# Add-OnV20-final.net
KiCad netlist of a schematic drawn in EAGLE
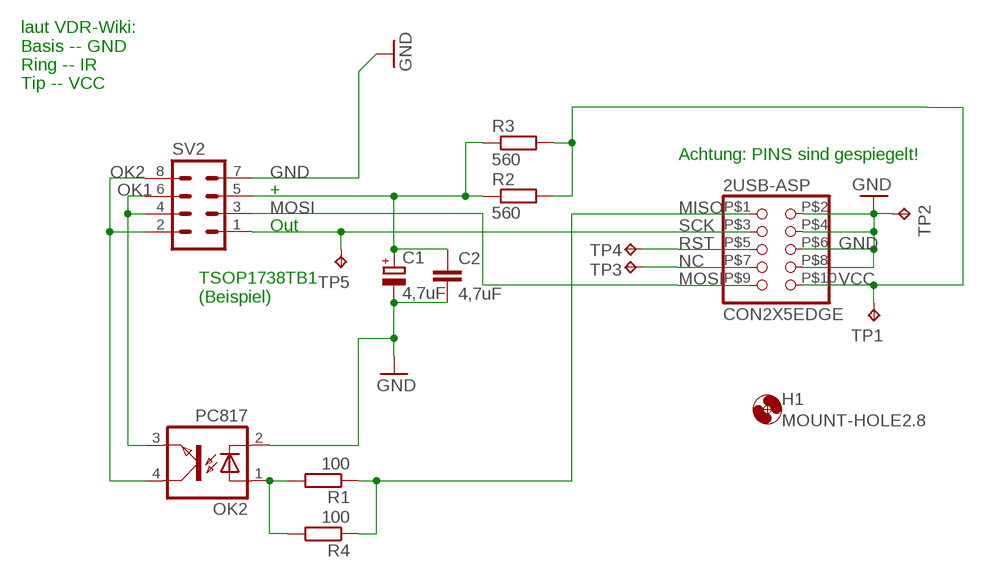
[diagram p0: schematic, sheet 1]

(export (version "E")
  (design (tool "Eeschema 10.0.6"))
  (components
    (comp (ref "2USB-ASP")
      (value "CON2X5EDGE")
      (footprint "eagle-import:CON2X5EDGE")
      (libsource (lib "eagle-import") (part "CON2X5EDGE"))
    )
    (comp (ref "C1")
      (value "4,7uF")
      (footprint "eagle-import:E1,8-4")
      (libsource (lib "eagle-import") (part "CPOL-EUE1.8-4"))
    )
    (comp (ref "C2")
      (value "4,7uF")
      (footprint "eagle-import:C1206K")
      (libsource (lib "eagle-import") (part "C-EUC1206K"))
    )
    (comp (ref "H1")
      (value "MOUNT-HOLE2.8")
      (footprint "eagle-import:2,8")
      (libsource (lib "eagle-import") (part "MOUNT-HOLE2.8"))
    )
    (comp (ref "OK2")
      (value "PC817")
      (footprint "eagle-import:DIL04")
      (fields (field (name "MPN") "PC817X4J000F"))
      (libsource (lib "eagle-import") (part "PC817"))
    )
    (comp (ref "R1")
      (value "100")
      (footprint "eagle-import:0204_7")
      (libsource (lib "eagle-import") (part "R-EU_0204/7"))
    )
    (comp (ref "R2")
      (value "560")
      (footprint "eagle-import:0204_7")
      (libsource (lib "eagle-import") (part "R-EU_0204/7"))
    )
    (comp (ref "R3")
      (value "560")
      (footprint "eagle-import:R0805W")
      (libsource (lib "eagle-import") (part "R-EU_R0805W"))
    )
    (comp (ref "R4")
      (value "100")
      (footprint "eagle-import:R0805W")
      (libsource (lib "eagle-import") (part "R-EU_R0805W"))
    )
    (comp (ref "SV2")
      (value "MA04-2")
      (footprint "eagle-import:MA04-2")
      (libsource (lib "eagle-import") (part "MA04-2"))
    )
    (comp (ref "TP1")
      (value "TPB1,27")
      (footprint "eagle-import:B1,27")
      (libsource (lib "eagle-import") (part "TPB1,27"))
    )
    (comp (ref "TP2")
      (value "TPB1,27")
      (footprint "eagle-import:B1,27")
      (libsource (lib "eagle-import") (part "TPB1,27"))
    )
    (comp (ref "TP3")
      (value "TPB1,27")
      (footprint "eagle-import:B1,27")
      (libsource (lib "eagle-import") (part "TPB1,27"))
    )
    (comp (ref "TP4")
      (value "TPB1,27")
      (footprint "eagle-import:B1,27")
      (libsource (lib "eagle-import") (part "TPB1,27"))
    )
    (comp (ref "TP5")
      (value "TPB1,27")
      (footprint "eagle-import:B1,27")
      (libsource (lib "eagle-import") (part "TPB1,27"))
    )
  )
  (nets
    (net (code "1") (name "/MISO") (class "Default")
      (node (ref "2USB-ASP") (pin "P$1") (pinfunction "1_P$1") (pintype "passive"))
      (node (ref "R1") (pin "1") (pinfunction "1_1") (pintype "passive"))
      (node (ref "R4") (pin "1") (pinfunction "1_1") (pintype "passive"))
    )
    (net (code "2") (name "/MOSI") (class "Default")
      (node (ref "2USB-ASP") (pin "P$9") (pinfunction "9_P$9") (pintype "passive"))
      (node (ref "SV2") (pin "3") (pinfunction "3_3") (pintype "passive"))
    )
    (net (code "3") (name "/NC") (class "Default")
      (node (ref "2USB-ASP") (pin "P$7") (pinfunction "7_P$7") (pintype "passive"))
      (node (ref "TP3") (pin "TP") (pinfunction "TP_TP") (pintype "input"))
    )
    (net (code "4") (name "/OK1") (class "Default")
      (node (ref "OK2") (pin "3") (pinfunction "EMIT_3") (pintype "passive"))
      (node (ref "SV2") (pin "4") (pinfunction "4_4") (pintype "passive"))
      (node (ref "SV2") (pin "6") (pinfunction "6_6") (pintype "passive"))
    )
    (net (code "5") (name "/OK2") (class "Default")
      (node (ref "OK2") (pin "4") (pinfunction "COL_4") (pintype "passive"))
      (node (ref "SV2") (pin "2") (pinfunction "2_2") (pintype "passive"))
      (node (ref "SV2") (pin "8") (pinfunction "8_8") (pintype "passive"))
    )
    (net (code "6") (name "/RST") (class "Default")
      (node (ref "2USB-ASP") (pin "P$5") (pinfunction "5_P$5") (pintype "passive"))
      (node (ref "TP4") (pin "TP") (pinfunction "TP_TP") (pintype "input"))
    )
    (net (code "7") (name "/SCK") (class "Default")
      (node (ref "2USB-ASP") (pin "P$3") (pinfunction "3_P$3") (pintype "passive"))
      (node (ref "SV2") (pin "1") (pinfunction "1_1") (pintype "passive"))
      (node (ref "TP5") (pin "TP") (pinfunction "TP_TP") (pintype "input"))
    )
    (net (code "8") (name "/VCC") (class "Default")
      (node (ref "2USB-ASP") (pin "P$10") (pinfunction "10_P$10") (pintype "passive"))
      (node (ref "R2") (pin "2") (pinfunction "2_2") (pintype "passive"))
      (node (ref "R3") (pin "2") (pinfunction "2_2") (pintype "passive"))
      (node (ref "TP1") (pin "TP") (pinfunction "TP_TP") (pintype "input"))
    )
    (net (code "9") (name "GND") (class "Default")
      (node (ref "2USB-ASP") (pin "P$2") (pinfunction "2_P$2") (pintype "passive"))
      (node (ref "2USB-ASP") (pin "P$4") (pinfunction "4_P$4") (pintype "passive"))
      (node (ref "2USB-ASP") (pin "P$6") (pinfunction "6_P$6") (pintype "passive"))
      (node (ref "2USB-ASP") (pin "P$8") (pinfunction "8_P$8") (pintype "passive"))
      (node (ref "C1") (pin "-") (pinfunction "-_-") (pintype "passive"))
      (node (ref "C2") (pin "2") (pinfunction "2_2") (pintype "passive"))
      (node (ref "OK2") (pin "2") (pinfunction "C_2") (pintype "passive"))
      (node (ref "SV2") (pin "7") (pinfunction "7_7") (pintype "passive"))
      (node (ref "TP2") (pin "TP") (pinfunction "TP_TP") (pintype "input"))
    )
    (net (code "10") (name "Net-(C1-Pad+)") (class "Default")
      (node (ref "C1") (pin "+") (pinfunction "+_+") (pintype "passive"))
      (node (ref "C2") (pin "1") (pinfunction "1_1") (pintype "passive"))
      (node (ref "R2") (pin "1") (pinfunction "1_1") (pintype "passive"))
      (node (ref "R3") (pin "1") (pinfunction "1_1") (pintype "passive"))
      (node (ref "SV2") (pin "5") (pinfunction "5_5") (pintype "passive"))
    )
    (net (code "11") (name "Net-(OK2-A)") (class "Default")
      (node (ref "OK2") (pin "1") (pinfunction "A_1") (pintype "passive"))
      (node (ref "R1") (pin "2") (pinfunction "2_2") (pintype "passive"))
      (node (ref "R4") (pin "2") (pinfunction "2_2") (pintype "passive"))
    )
  )
)
